# 2_MCU.net
KiCad netlist of a schematic drawn in Altium Designer
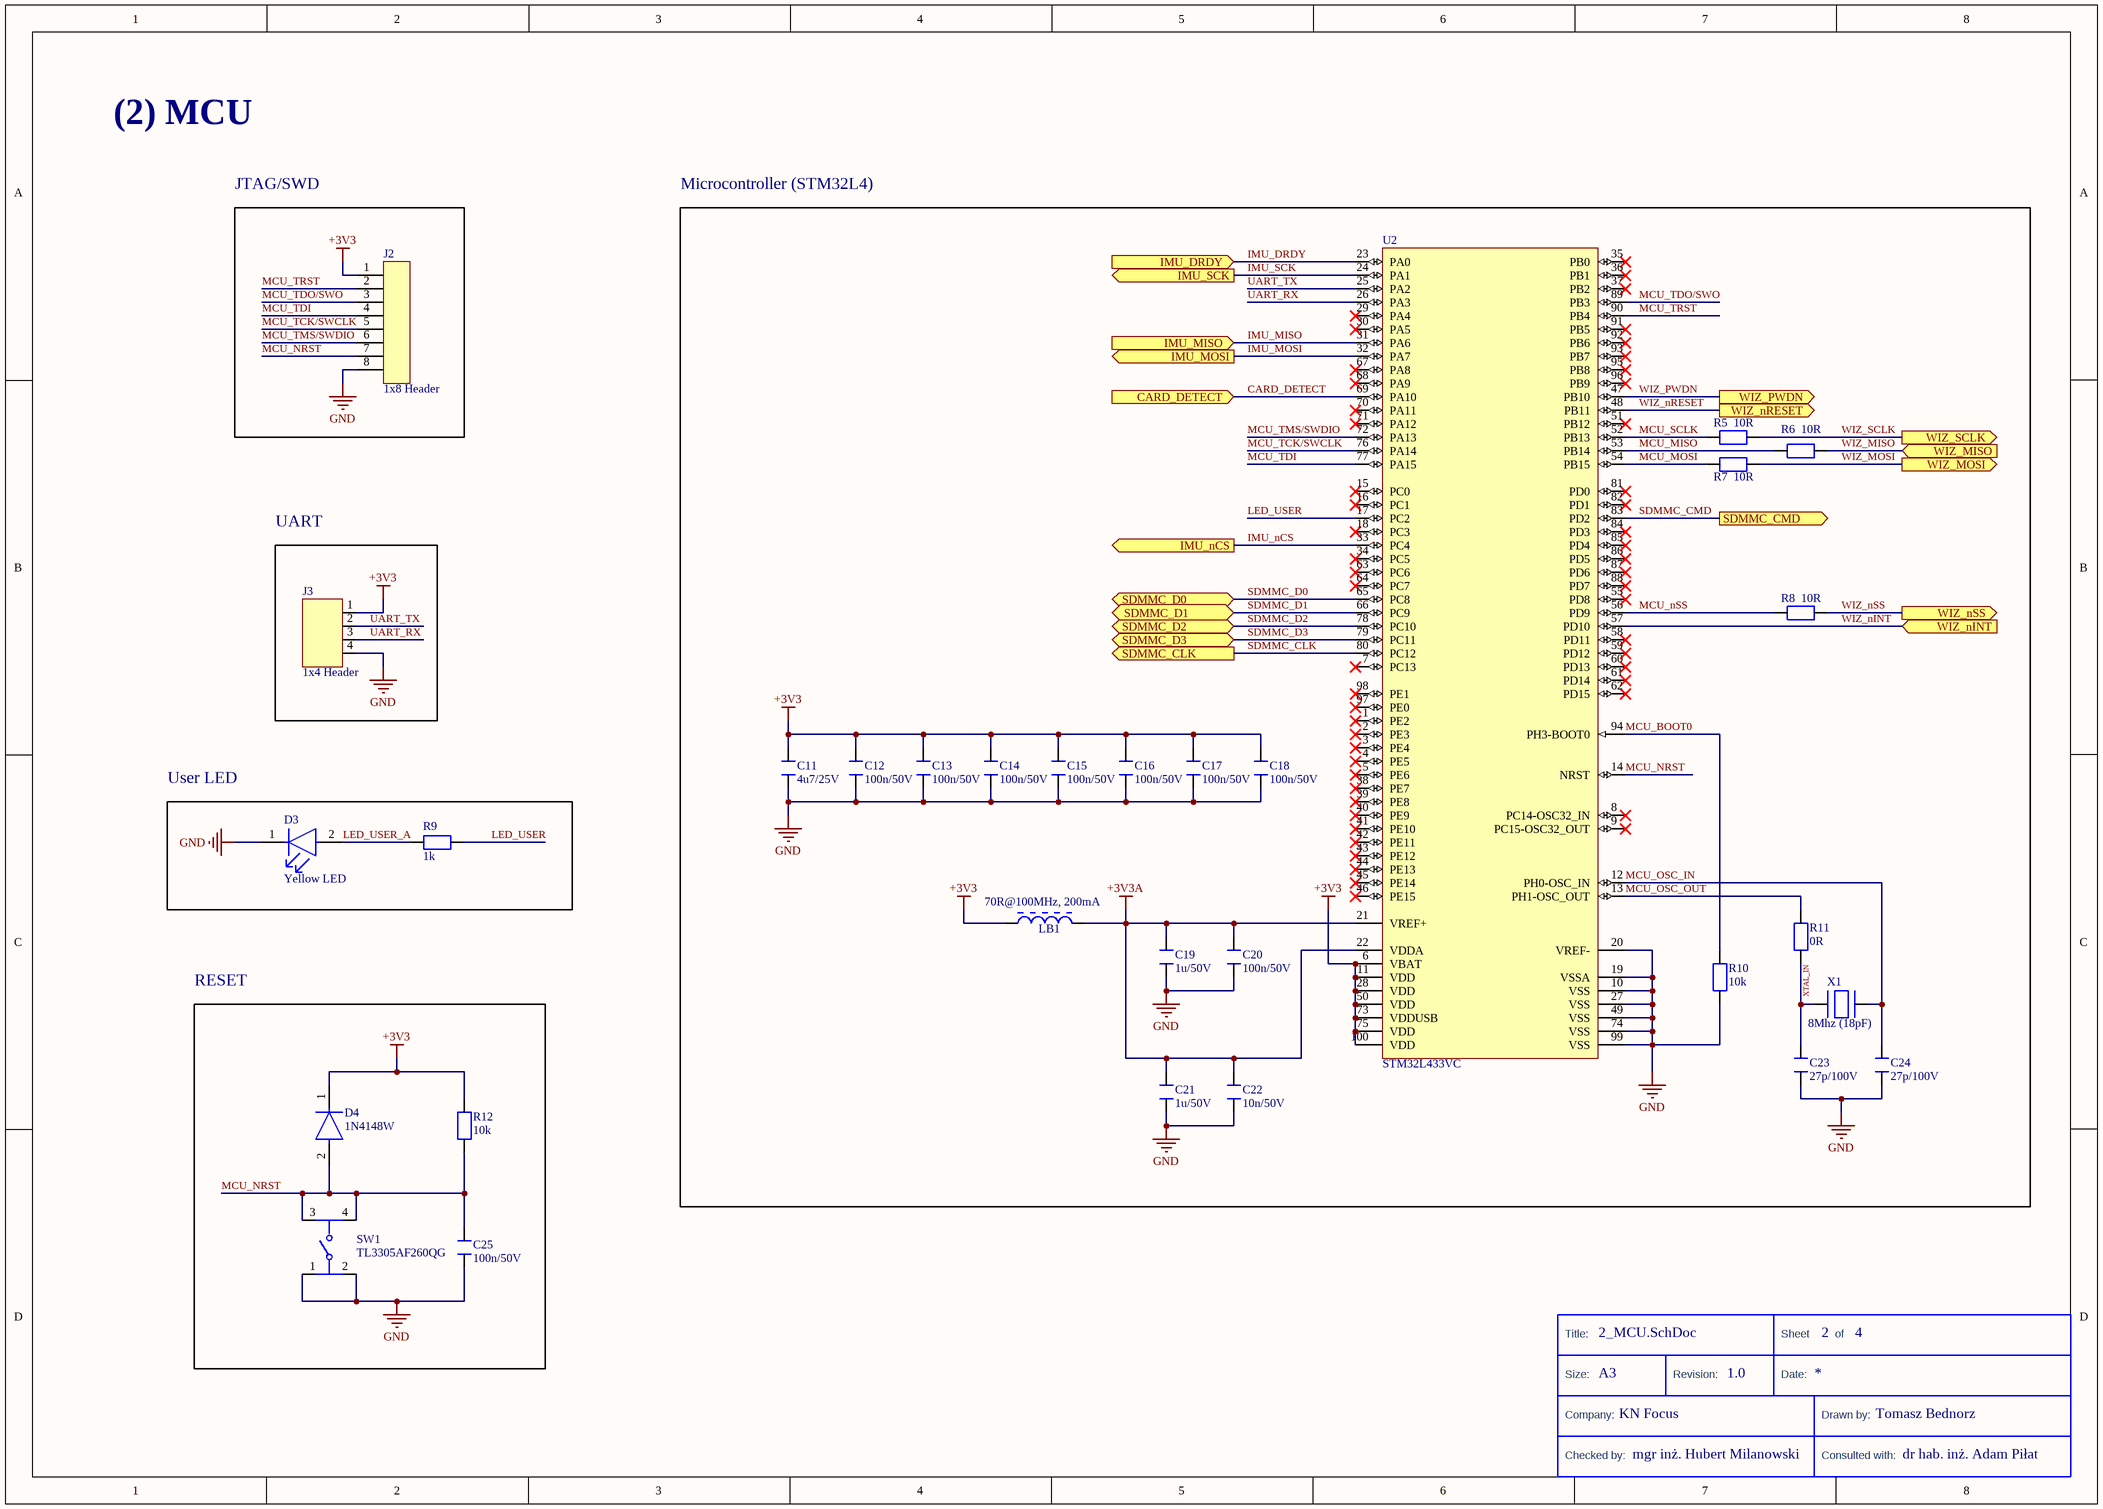
[diagram p0: 2_MCU.SchDoc]

(export (version "E")
  (design (tool "Eeschema 10.0.6"))
  (components
    (comp (ref "C11")
      (value "4u7/25V")
      (footprint "CAP_1206")
      (description "Generic 1206/3216 capacitor")
      (libsource (lib "SymbolLib") (part "CAP_1206"))
    )
    (comp (ref "C12")
      (value "100n/50V")
      (footprint "CAP_1206")
      (description "Generic 1206/3216 capacitor")
      (libsource (lib "SymbolLib") (part "CAP_1206"))
    )
    (comp (ref "C13")
      (value "100n/50V")
      (footprint "CAP_1206")
      (description "Generic 1206/3216 capacitor")
      (libsource (lib "SymbolLib") (part "CAP_1206"))
    )
    (comp (ref "C14")
      (value "100n/50V")
      (footprint "CAP_1206")
      (description "Generic 1206/3216 capacitor")
      (libsource (lib "SymbolLib") (part "CAP_1206"))
    )
    (comp (ref "C15")
      (value "100n/50V")
      (footprint "CAP_1206")
      (description "Generic 1206/3216 capacitor")
      (libsource (lib "SymbolLib") (part "CAP_1206"))
    )
    (comp (ref "C16")
      (value "100n/50V")
      (footprint "CAP_1206")
      (description "Generic 1206/3216 capacitor")
      (libsource (lib "SymbolLib") (part "CAP_1206"))
    )
    (comp (ref "C17")
      (value "100n/50V")
      (footprint "CAP_1206")
      (description "Generic 1206/3216 capacitor")
      (libsource (lib "SymbolLib") (part "CAP_1206"))
    )
    (comp (ref "C18")
      (value "100n/50V")
      (footprint "CAP_1206")
      (description "Generic 1206/3216 capacitor")
      (libsource (lib "SymbolLib") (part "CAP_1206"))
    )
    (comp (ref "C19")
      (value "1u/50V")
      (footprint "CAP_1206")
      (description "Generic 1206/3216 capacitor")
      (libsource (lib "SymbolLib") (part "CAP_1206"))
    )
    (comp (ref "C20")
      (value "100n/50V")
      (footprint "CAP_1206")
      (description "Generic 1206/3216 capacitor")
      (libsource (lib "SymbolLib") (part "CAP_1206"))
    )
    (comp (ref "C21")
      (value "1u/50V")
      (footprint "CAP_1206")
      (description "Generic 1206/3216 capacitor")
      (libsource (lib "SymbolLib") (part "CAP_1206"))
    )
    (comp (ref "C22")
      (value "10n/50V")
      (footprint "CAP_1206")
      (description "Generic 1206/3216 capacitor")
      (libsource (lib "SymbolLib") (part "CAP_1206"))
    )
    (comp (ref "C23")
      (value "27p/100V")
      (footprint "CAP_1206")
      (description "Generic 1206/3216 capacitor")
      (libsource (lib "SymbolLib") (part "CAP_1206"))
    )
    (comp (ref "C24")
      (value "27p/100V")
      (footprint "CAP_1206")
      (description "Generic 1206/3216 capacitor")
      (libsource (lib "SymbolLib") (part "CAP_1206"))
    )
    (comp (ref "C25")
      (value "100n/50V")
      (footprint "CAP_1206")
      (description "Generic 1206/3216 capacitor")
      (libsource (lib "SymbolLib") (part "CAP_1206"))
    )
    (comp (ref "D3")
      (value "Yellow LED")
      (footprint "FP-LTST-C150KSKT-MFG")
      (description "LED YELLOW CLEAR 1206 SMD")
      (libsource (lib "Altium Content Vault") (part "8706943c75ba83719d021d2fdc84c58"))
    )
    (comp (ref "D4")
      (value "1N4148W")
      (footprint "FP-SOD-123-IPC_A")
      (description "DIODE GEN PURP 100V 150MA SOD123")
      (libsource (lib "Altium Content Vault") (part "d7152d700b627762746794eb795d46e"))
    )
    (comp (ref "J2")
      (value "1x8 Header")
      (footprint "1x8 Header")
      (description "1x8 Header,Through Hole (Goldpin 2.54m)")
      (libsource (lib "SymbolLib") (part "1x8 Header"))
    )
    (comp (ref "J3")
      (value "1x4 Header")
      (footprint "1x4 Header (Goldpin 2.54mm)")
      (description "1x4 Header,Through Hole (Goldpin 2.54mm)")
      (libsource (lib "SymbolLib") (part "1x4 Header (Goldpin 2.54mm)"))
    )
    (comp (ref "LB1")
      (value "70R@100MHz, 200mA")
      (footprint "MURA-BLM31A_L")
      (description "Chip Bead, 100 MHz, 200 mA, -55 to 125 degC, 2-Pin SMD (1206), RoHS, Tape and Reel")
      (fields (field (name "MANUFACTURER") "Murata") (field (name "TOLERANCE") "25%"))
      (libsource (lib "Altium Content Vault") (part "IND-FB-2"))
    )
    (comp (ref "R5")
      (value "10R")
      (footprint "RES_1206")
      (description "Generic 1206/3216 resistor")
      (libsource (lib "SymbolLib") (part "RES_1206"))
    )
    (comp (ref "R6")
      (value "10R")
      (footprint "RES_1206")
      (description "Generic 1206/3216 resistor")
      (libsource (lib "SymbolLib") (part "RES_1206"))
    )
    (comp (ref "R7")
      (value "10R")
      (footprint "RES_1206")
      (description "Generic 1206/3216 resistor")
      (libsource (lib "SymbolLib") (part "RES_1206"))
    )
    (comp (ref "R8")
      (value "10R")
      (footprint "RES_1206")
      (description "Generic 1206/3216 resistor")
      (libsource (lib "SymbolLib") (part "RES_1206"))
    )
    (comp (ref "R9")
      (value "1k")
      (footprint "RES_1206")
      (description "Generic 1206/3216 resistor")
      (libsource (lib "SymbolLib") (part "RES_1206"))
    )
    (comp (ref "R10")
      (value "10k")
      (footprint "RES_1206")
      (description "Generic 1206/3216 resistor")
      (libsource (lib "SymbolLib") (part "RES_1206"))
    )
    (comp (ref "R11")
      (value "0R")
      (footprint "RES_1206")
      (description "Generic 1206/3216 resistor")
      (libsource (lib "SymbolLib") (part "RES_1206"))
    )
    (comp (ref "R12")
      (value "10k")
      (footprint "RES_1206")
      (description "Generic 1206/3216 resistor")
      (libsource (lib "SymbolLib") (part "RES_1206"))
    )
    (comp (ref "SW1")
      (value "TL3305AF260QG")
      (footprint "FP-TL3305AF260QG-MFG")
      (description "SWITCH TACTILE SPST-NO 50MA 12V")
      (libsource (lib "Altium Content Vault") (part "b8895f3f4cefb76e1819d2863dba89b"))
    )
    (comp (ref "U2")
      (value "STM32L433VC")
      (footprint "LQFP100")
      (description "STM32L433RC, 80MHz, Coretx-M4")
      (libsource (lib "SymbolLib") (part "STM32L433VC"))
    )
    (comp (ref "X1")
      (value "8Mhz (18pF)")
      (footprint "XTAL-12.5x4.8")
      (description "XTAL-8MHz")
      (libsource (lib "SymbolLib") (part "XTAL-8MHz"))
    )
  )
  (nets
    (net (code "1") (name "+3V3") (class "Default")
      (node (ref "C11") (pin "2") (pinfunction "2_2") (pintype "passive"))
      (node (ref "C12") (pin "2") (pinfunction "2_2") (pintype "passive"))
      (node (ref "C13") (pin "2") (pinfunction "2_2") (pintype "passive"))
      (node (ref "C14") (pin "2") (pinfunction "2_2") (pintype "passive"))
      (node (ref "C15") (pin "2") (pinfunction "2_2") (pintype "passive"))
      (node (ref "C16") (pin "2") (pinfunction "2_2") (pintype "passive"))
      (node (ref "C17") (pin "2") (pinfunction "2_2") (pintype "passive"))
      (node (ref "C18") (pin "2") (pinfunction "2_2") (pintype "passive"))
      (node (ref "D4") (pin "1") (pinfunction "C_1") (pintype "passive"))
      (node (ref "J2") (pin "1") (pintype "passive"))
      (node (ref "J3") (pin "1") (pinfunction "1_1") (pintype "passive"))
      (node (ref "LB1") (pin "1") (pinfunction "1_1") (pintype "passive"))
      (node (ref "R12") (pin "2") (pinfunction "2_2") (pintype "passive"))
      (node (ref "U2") (pin "100") (pinfunction "VDD_100") (pintype "power_in"))
      (node (ref "U2") (pin "11") (pinfunction "VDD_11") (pintype "power_in"))
      (node (ref "U2") (pin "28") (pinfunction "VDD_28") (pintype "power_in"))
      (node (ref "U2") (pin "50") (pinfunction "VDD_50") (pintype "power_in"))
      (node (ref "U2") (pin "6") (pinfunction "VBAT_6") (pintype "power_in"))
      (node (ref "U2") (pin "73") (pinfunction "VDDUSB_73") (pintype "power_in"))
      (node (ref "U2") (pin "75") (pinfunction "VDD_75") (pintype "power_in"))
    )
    (net (code "2") (name "+3V3A") (class "Default")
      (node (ref "C19") (pin "2") (pinfunction "2_2") (pintype "passive"))
      (node (ref "C20") (pin "2") (pinfunction "2_2") (pintype "passive"))
      (node (ref "C21") (pin "2") (pinfunction "2_2") (pintype "passive"))
      (node (ref "C22") (pin "2") (pinfunction "2_2") (pintype "passive"))
      (node (ref "LB1") (pin "2") (pinfunction "2_2") (pintype "passive"))
      (node (ref "U2") (pin "21") (pinfunction "VREF+_21") (pintype "power_in"))
      (node (ref "U2") (pin "22") (pinfunction "VDDA_22") (pintype "power_in"))
    )
    (net (code "3") (name "/CARD_DETECT") (class "Default")
      (node (ref "U2") (pin "69") (pinfunction "PA10_69") (pintype "bidirectional"))
    )
    (net (code "4") (name "/IMU_DRDY") (class "Default")
      (node (ref "U2") (pin "23") (pinfunction "PA0_23") (pintype "bidirectional"))
    )
    (net (code "5") (name "/IMU_MISO") (class "Default")
      (node (ref "U2") (pin "31") (pinfunction "PA6_31") (pintype "bidirectional"))
    )
    (net (code "6") (name "/IMU_MOSI") (class "Default")
      (node (ref "U2") (pin "32") (pinfunction "PA7_32") (pintype "bidirectional"))
    )
    (net (code "7") (name "/IMU_SCK") (class "Default")
      (node (ref "U2") (pin "24") (pinfunction "PA1_24") (pintype "bidirectional"))
    )
    (net (code "8") (name "/IMU_nCS") (class "Default")
      (node (ref "U2") (pin "33") (pinfunction "PC4_33") (pintype "bidirectional"))
    )
    (net (code "9") (name "/LED_USER") (class "Default")
      (node (ref "R9") (pin "1") (pinfunction "1_1") (pintype "passive"))
      (node (ref "U2") (pin "17") (pinfunction "PC2_17") (pintype "bidirectional"))
    )
    (net (code "10") (name "/LED_USER_A") (class "Default")
      (node (ref "D3") (pin "2") (pinfunction "A_2") (pintype "passive"))
      (node (ref "R9") (pin "2") (pinfunction "2_2") (pintype "passive"))
    )
    (net (code "11") (name "/MCU_BOOT0") (class "Default")
      (node (ref "R10") (pin "2") (pinfunction "2_2") (pintype "passive"))
      (node (ref "U2") (pin "94") (pinfunction "PH3-BOOT0_94") (pintype "input"))
    )
    (net (code "12") (name "/MCU_MISO") (class "Default")
      (node (ref "R6") (pin "2") (pinfunction "2_2") (pintype "passive"))
      (node (ref "U2") (pin "53") (pinfunction "PB14_53") (pintype "bidirectional"))
    )
    (net (code "13") (name "/MCU_MOSI") (class "Default")
      (node (ref "R7") (pin "2") (pinfunction "2_2") (pintype "passive"))
      (node (ref "U2") (pin "54") (pinfunction "PB15_54") (pintype "bidirectional"))
    )
    (net (code "14") (name "/MCU_NRST") (class "Default")
      (node (ref "C25") (pin "2") (pinfunction "2_2") (pintype "passive"))
      (node (ref "D4") (pin "2") (pinfunction "A_2") (pintype "passive"))
      (node (ref "J2") (pin "7") (pintype "passive"))
      (node (ref "R12") (pin "1") (pinfunction "1_1") (pintype "passive"))
      (node (ref "SW1") (pin "3") (pinfunction "3_3") (pintype "passive"))
      (node (ref "SW1") (pin "4") (pinfunction "4_4") (pintype "passive"))
      (node (ref "U2") (pin "14") (pinfunction "NRST_14") (pintype "bidirectional"))
    )
    (net (code "15") (name "/MCU_OSC_IN") (class "Default")
      (node (ref "C24") (pin "2") (pinfunction "2_2") (pintype "passive"))
      (node (ref "U2") (pin "12") (pinfunction "PH0-OSC_IN_12") (pintype "bidirectional"))
      (node (ref "X1") (pin "2") (pinfunction "2_2") (pintype "passive"))
    )
    (net (code "16") (name "/MCU_OSC_OUT") (class "Default")
      (node (ref "R11") (pin "1") (pinfunction "1_1") (pintype "passive"))
      (node (ref "U2") (pin "13") (pinfunction "PH1-OSC_OUT_13") (pintype "bidirectional"))
    )
    (net (code "17") (name "/MCU_SCLK") (class "Default")
      (node (ref "R5") (pin "2") (pinfunction "2_2") (pintype "passive"))
      (node (ref "U2") (pin "52") (pinfunction "PB13_52") (pintype "bidirectional"))
    )
    (net (code "18") (name "/MCU_TCK{slash}SWCLK") (class "Default")
      (node (ref "J2") (pin "5") (pintype "passive"))
      (node (ref "U2") (pin "76") (pinfunction "PA14_76") (pintype "bidirectional"))
    )
    (net (code "19") (name "/MCU_TDI") (class "Default")
      (node (ref "J2") (pin "4") (pintype "passive"))
      (node (ref "U2") (pin "77") (pinfunction "PA15_77") (pintype "bidirectional"))
    )
    (net (code "20") (name "/MCU_TDO{slash}SWO") (class "Default")
      (node (ref "J2") (pin "3") (pintype "passive"))
      (node (ref "U2") (pin "89") (pinfunction "PB3_89") (pintype "bidirectional"))
    )
    (net (code "21") (name "/MCU_TMS{slash}SWDIO") (class "Default")
      (node (ref "J2") (pin "6") (pintype "passive"))
      (node (ref "U2") (pin "72") (pinfunction "PA13_72") (pintype "bidirectional"))
    )
    (net (code "22") (name "/MCU_TRST") (class "Default")
      (node (ref "J2") (pin "2") (pintype "passive"))
      (node (ref "U2") (pin "90") (pinfunction "PB4_90") (pintype "bidirectional"))
    )
    (net (code "23") (name "/MCU_nSS") (class "Default")
      (node (ref "R8") (pin "2") (pinfunction "2_2") (pintype "passive"))
      (node (ref "U2") (pin "56") (pinfunction "PD9_56") (pintype "bidirectional"))
    )
    (net (code "24") (name "/SDMMC_CLK") (class "Default")
      (node (ref "U2") (pin "80") (pinfunction "PC12_80") (pintype "bidirectional"))
    )
    (net (code "25") (name "/SDMMC_CMD") (class "Default")
      (node (ref "U2") (pin "83") (pinfunction "PD2_83") (pintype "bidirectional"))
    )
    (net (code "26") (name "/SDMMC_D0") (class "Default")
      (node (ref "U2") (pin "65") (pinfunction "PC8_65") (pintype "bidirectional"))
    )
    (net (code "27") (name "/SDMMC_D1") (class "Default")
      (node (ref "U2") (pin "66") (pinfunction "PC9_66") (pintype "bidirectional"))
    )
    (net (code "28") (name "/SDMMC_D2") (class "Default")
      (node (ref "U2") (pin "78") (pinfunction "PC10_78") (pintype "bidirectional"))
    )
    (net (code "29") (name "/SDMMC_D3") (class "Default")
      (node (ref "U2") (pin "79") (pinfunction "PC11_79") (pintype "bidirectional"))
    )
    (net (code "30") (name "/UART_RX") (class "Default")
      (node (ref "J3") (pin "3") (pinfunction "3_3") (pintype "passive"))
      (node (ref "U2") (pin "26") (pinfunction "PA3_26") (pintype "bidirectional"))
    )
    (net (code "31") (name "/UART_TX") (class "Default")
      (node (ref "J3") (pin "2") (pinfunction "2_2") (pintype "passive"))
      (node (ref "U2") (pin "25") (pinfunction "PA2_25") (pintype "bidirectional"))
    )
    (net (code "32") (name "/WIZ_MISO") (class "Default")
      (node (ref "R6") (pin "1") (pinfunction "1_1") (pintype "passive"))
    )
    (net (code "33") (name "/WIZ_MOSI") (class "Default")
      (node (ref "R7") (pin "1") (pinfunction "1_1") (pintype "passive"))
    )
    (net (code "34") (name "/WIZ_PWDN") (class "Default")
      (node (ref "U2") (pin "47") (pinfunction "PB10_47") (pintype "bidirectional"))
    )
    (net (code "35") (name "/WIZ_SCLK") (class "Default")
      (node (ref "R5") (pin "1") (pinfunction "1_1") (pintype "passive"))
    )
    (net (code "36") (name "/WIZ_nINT") (class "Default")
      (node (ref "U2") (pin "57") (pinfunction "PD10_57") (pintype "bidirectional"))
    )
    (net (code "37") (name "/WIZ_nRESET") (class "Default")
      (node (ref "U2") (pin "48") (pinfunction "PB11_48") (pintype "bidirectional"))
    )
    (net (code "38") (name "/WIZ_nSS") (class "Default")
      (node (ref "R8") (pin "1") (pinfunction "1_1") (pintype "passive"))
    )
    (net (code "39") (name "/XTAL_IN") (class "Default")
      (node (ref "C23") (pin "2") (pinfunction "2_2") (pintype "passive"))
      (node (ref "R11") (pin "2") (pinfunction "2_2") (pintype "passive"))
      (node (ref "X1") (pin "1") (pinfunction "1_1") (pintype "passive"))
    )
    (net (code "40") (name "GND") (class "Default")
      (node (ref "C11") (pin "1") (pinfunction "1_1") (pintype "passive"))
      (node (ref "C12") (pin "1") (pinfunction "1_1") (pintype "passive"))
      (node (ref "C13") (pin "1") (pinfunction "1_1") (pintype "passive"))
      (node (ref "C14") (pin "1") (pinfunction "1_1") (pintype "passive"))
      (node (ref "C15") (pin "1") (pinfunction "1_1") (pintype "passive"))
      (node (ref "C16") (pin "1") (pinfunction "1_1") (pintype "passive"))
      (node (ref "C17") (pin "1") (pinfunction "1_1") (pintype "passive"))
      (node (ref "C18") (pin "1") (pinfunction "1_1") (pintype "passive"))
      (node (ref "C19") (pin "1") (pinfunction "1_1") (pintype "passive"))
      (node (ref "C20") (pin "1") (pinfunction "1_1") (pintype "passive"))
      (node (ref "C21") (pin "1") (pinfunction "1_1") (pintype "passive"))
      (node (ref "C22") (pin "1") (pinfunction "1_1") (pintype "passive"))
      (node (ref "C23") (pin "1") (pinfunction "1_1") (pintype "passive"))
      (node (ref "C24") (pin "1") (pinfunction "1_1") (pintype "passive"))
      (node (ref "C25") (pin "1") (pinfunction "1_1") (pintype "passive"))
      (node (ref "D3") (pin "1") (pinfunction "C_1") (pintype "passive"))
      (node (ref "J2") (pin "8") (pintype "passive"))
      (node (ref "J3") (pin "4") (pinfunction "4_4") (pintype "passive"))
      (node (ref "R10") (pin "1") (pinfunction "1_1") (pintype "passive"))
      (node (ref "SW1") (pin "1") (pinfunction "1_1") (pintype "passive"))
      (node (ref "SW1") (pin "2") (pinfunction "2_2") (pintype "passive"))
      (node (ref "U2") (pin "10") (pinfunction "VSS_10") (pintype "power_in"))
      (node (ref "U2") (pin "19") (pinfunction "VSSA_19") (pintype "power_in"))
      (node (ref "U2") (pin "20") (pinfunction "VREF-_20") (pintype "power_in"))
      (node (ref "U2") (pin "27") (pinfunction "VSS_27") (pintype "power_in"))
      (node (ref "U2") (pin "49") (pinfunction "VSS_49") (pintype "power_in"))
      (node (ref "U2") (pin "74") (pinfunction "VSS_74") (pintype "power_in"))
      (node (ref "U2") (pin "99") (pinfunction "VSS_99") (pintype "power_in"))
    )
    (net (code "41") (name "unconnected-(U2-PA4-Pad29)") (class "Default")
      (node (ref "U2") (pin "29") (pinfunction "PA4_29") (pintype "bidirectional+no_connect"))
    )
    (net (code "42") (name "unconnected-(U2-PA5-Pad30)") (class "Default")
      (node (ref "U2") (pin "30") (pinfunction "PA5_30") (pintype "bidirectional+no_connect"))
    )
    (net (code "43") (name "unconnected-(U2-PA8-Pad67)") (class "Default")
      (node (ref "U2") (pin "67") (pinfunction "PA8_67") (pintype "bidirectional+no_connect"))
    )
    (net (code "44") (name "unconnected-(U2-PA9-Pad68)") (class "Default")
      (node (ref "U2") (pin "68") (pinfunction "PA9_68") (pintype "bidirectional+no_connect"))
    )
    (net (code "45") (name "unconnected-(U2-PA11-Pad70)") (class "Default")
      (node (ref "U2") (pin "70") (pinfunction "PA11_70") (pintype "bidirectional+no_connect"))
    )
    (net (code "46") (name "unconnected-(U2-PA12-Pad71)") (class "Default")
      (node (ref "U2") (pin "71") (pinfunction "PA12_71") (pintype "bidirectional+no_connect"))
    )
    (net (code "47") (name "unconnected-(U2-PB0-Pad35)") (class "Default")
      (node (ref "U2") (pin "35") (pinfunction "PB0_35") (pintype "bidirectional+no_connect"))
    )
    (net (code "48") (name "unconnected-(U2-PB1-Pad36)") (class "Default")
      (node (ref "U2") (pin "36") (pinfunction "PB1_36") (pintype "bidirectional+no_connect"))
    )
    (net (code "49") (name "unconnected-(U2-PB2-Pad37)") (class "Default")
      (node (ref "U2") (pin "37") (pinfunction "PB2_37") (pintype "bidirectional+no_connect"))
    )
    (net (code "50") (name "unconnected-(U2-PB5-Pad91)") (class "Default")
      (node (ref "U2") (pin "91") (pinfunction "PB5_91") (pintype "bidirectional+no_connect"))
    )
    (net (code "51") (name "unconnected-(U2-PB6-Pad92)") (class "Default")
      (node (ref "U2") (pin "92") (pinfunction "PB6_92") (pintype "bidirectional+no_connect"))
    )
    (net (code "52") (name "unconnected-(U2-PB7-Pad93)") (class "Default")
      (node (ref "U2") (pin "93") (pinfunction "PB7_93") (pintype "bidirectional+no_connect"))
    )
    (net (code "53") (name "unconnected-(U2-PB8-Pad95)") (class "Default")
      (node (ref "U2") (pin "95") (pinfunction "PB8_95") (pintype "bidirectional+no_connect"))
    )
    (net (code "54") (name "unconnected-(U2-PB9-Pad96)") (class "Default")
      (node (ref "U2") (pin "96") (pinfunction "PB9_96") (pintype "bidirectional+no_connect"))
    )
    (net (code "55") (name "unconnected-(U2-PB12-Pad51)") (class "Default")
      (node (ref "U2") (pin "51") (pinfunction "PB12_51") (pintype "bidirectional+no_connect"))
    )
    (net (code "56") (name "unconnected-(U2-PC0-Pad15)") (class "Default")
      (node (ref "U2") (pin "15") (pinfunction "PC0_15") (pintype "bidirectional+no_connect"))
    )
    (net (code "57") (name "unconnected-(U2-PC1-Pad16)") (class "Default")
      (node (ref "U2") (pin "16") (pinfunction "PC1_16") (pintype "bidirectional+no_connect"))
    )
    (net (code "58") (name "unconnected-(U2-PC3-Pad18)") (class "Default")
      (node (ref "U2") (pin "18") (pinfunction "PC3_18") (pintype "bidirectional+no_connect"))
    )
    (net (code "59") (name "unconnected-(U2-PC5-Pad34)") (class "Default")
      (node (ref "U2") (pin "34") (pinfunction "PC5_34") (pintype "bidirectional+no_connect"))
    )
    (net (code "60") (name "unconnected-(U2-PC6-Pad63)") (class "Default")
      (node (ref "U2") (pin "63") (pinfunction "PC6_63") (pintype "bidirectional+no_connect"))
    )
    (net (code "61") (name "unconnected-(U2-PC7-Pad64)") (class "Default")
      (node (ref "U2") (pin "64") (pinfunction "PC7_64") (pintype "bidirectional+no_connect"))
    )
    (net (code "62") (name "unconnected-(U2-PC13-Pad7)") (class "Default")
      (node (ref "U2") (pin "7") (pinfunction "PC13_7") (pintype "bidirectional+no_connect"))
    )
    (net (code "63") (name "unconnected-(U2-PC14-OSC32_IN-Pad8)") (class "Default")
      (node (ref "U2") (pin "8") (pinfunction "PC14-OSC32_IN_8") (pintype "bidirectional+no_connect"))
    )
    (net (code "64") (name "unconnected-(U2-PC15-OSC32_OUT-Pad9)") (class "Default")
      (node (ref "U2") (pin "9") (pinfunction "PC15-OSC32_OUT_9") (pintype "bidirectional+no_connect"))
    )
    (net (code "65") (name "unconnected-(U2-PD0-Pad81)") (class "Default")
      (node (ref "U2") (pin "81") (pinfunction "PD0_81") (pintype "bidirectional+no_connect"))
    )
    (net (code "66") (name "unconnected-(U2-PD1-Pad82)") (class "Default")
      (node (ref "U2") (pin "82") (pinfunction "PD1_82") (pintype "bidirectional+no_connect"))
    )
    (net (code "67") (name "unconnected-(U2-PD3-Pad84)") (class "Default")
      (node (ref "U2") (pin "84") (pinfunction "PD3_84") (pintype "bidirectional+no_connect"))
    )
    (net (code "68") (name "unconnected-(U2-PD4-Pad85)") (class "Default")
      (node (ref "U2") (pin "85") (pinfunction "PD4_85") (pintype "bidirectional+no_connect"))
    )
    (net (code "69") (name "unconnected-(U2-PD5-Pad86)") (class "Default")
      (node (ref "U2") (pin "86") (pinfunction "PD5_86") (pintype "bidirectional+no_connect"))
    )
    (net (code "70") (name "unconnected-(U2-PD6-Pad87)") (class "Default")
      (node (ref "U2") (pin "87") (pinfunction "PD6_87") (pintype "bidirectional+no_connect"))
    )
    (net (code "71") (name "unconnected-(U2-PD7-Pad88)") (class "Default")
      (node (ref "U2") (pin "88") (pinfunction "PD7_88") (pintype "bidirectional+no_connect"))
    )
    (net (code "72") (name "unconnected-(U2-PD8-Pad55)") (class "Default")
      (node (ref "U2") (pin "55") (pinfunction "PD8_55") (pintype "bidirectional+no_connect"))
    )
    (net (code "73") (name "unconnected-(U2-PD11-Pad58)") (class "Default")
      (node (ref "U2") (pin "58") (pinfunction "PD11_58") (pintype "bidirectional+no_connect"))
    )
    (net (code "74") (name "unconnected-(U2-PD12-Pad59)") (class "Default")
      (node (ref "U2") (pin "59") (pinfunction "PD12_59") (pintype "bidirectional+no_connect"))
    )
    (net (code "75") (name "unconnected-(U2-PD13-Pad60)") (class "Default")
      (node (ref "U2") (pin "60") (pinfunction "PD13_60") (pintype "bidirectional+no_connect"))
    )
    (net (code "76") (name "unconnected-(U2-PD14-Pad61)") (class "Default")
      (node (ref "U2") (pin "61") (pinfunction "PD14_61") (pintype "bidirectional+no_connect"))
    )
    (net (code "77") (name "unconnected-(U2-PD15-Pad62)") (class "Default")
      (node (ref "U2") (pin "62") (pinfunction "PD15_62") (pintype "bidirectional+no_connect"))
    )
    (net (code "78") (name "unconnected-(U2-PE0-Pad97)") (class "Default")
      (node (ref "U2") (pin "97") (pinfunction "PE0_97") (pintype "bidirectional+no_connect"))
    )
    (net (code "79") (name "unconnected-(U2-PE1-Pad98)") (class "Default")
      (node (ref "U2") (pin "98") (pinfunction "PE1_98") (pintype "bidirectional+no_connect"))
    )
    (net (code "80") (name "unconnected-(U2-PE2-Pad1)") (class "Default")
      (node (ref "U2") (pin "1") (pinfunction "PE2_1") (pintype "bidirectional+no_connect"))
    )
    (net (code "81") (name "unconnected-(U2-PE3-Pad2)") (class "Default")
      (node (ref "U2") (pin "2") (pinfunction "PE3_2") (pintype "bidirectional+no_connect"))
    )
    (net (code "82") (name "unconnected-(U2-PE4-Pad3)") (class "Default")
      (node (ref "U2") (pin "3") (pinfunction "PE4_3") (pintype "bidirectional+no_connect"))
    )
    (net (code "83") (name "unconnected-(U2-PE5-Pad4)") (class "Default")
      (node (ref "U2") (pin "4") (pinfunction "PE5_4") (pintype "bidirectional+no_connect"))
    )
    (net (code "84") (name "unconnected-(U2-PE6-Pad5)") (class "Default")
      (node (ref "U2") (pin "5") (pinfunction "PE6_5") (pintype "bidirectional+no_connect"))
    )
    (net (code "85") (name "unconnected-(U2-PE7-Pad38)") (class "Default")
      (node (ref "U2") (pin "38") (pinfunction "PE7_38") (pintype "bidirectional+no_connect"))
    )
    (net (code "86") (name "unconnected-(U2-PE8-Pad39)") (class "Default")
      (node (ref "U2") (pin "39") (pinfunction "PE8_39") (pintype "bidirectional+no_connect"))
    )
    (net (code "87") (name "unconnected-(U2-PE9-Pad40)") (class "Default")
      (node (ref "U2") (pin "40") (pinfunction "PE9_40") (pintype "bidirectional+no_connect"))
    )
    (net (code "88") (name "unconnected-(U2-PE10-Pad41)") (class "Default")
      (node (ref "U2") (pin "41") (pinfunction "PE10_41") (pintype "bidirectional+no_connect"))
    )
    (net (code "89") (name "unconnected-(U2-PE11-Pad42)") (class "Default")
      (node (ref "U2") (pin "42") (pinfunction "PE11_42") (pintype "bidirectional+no_connect"))
    )
    (net (code "90") (name "unconnected-(U2-PE12-Pad43)") (class "Default")
      (node (ref "U2") (pin "43") (pinfunction "PE12_43") (pintype "bidirectional+no_connect"))
    )
    (net (code "91") (name "unconnected-(U2-PE13-Pad44)") (class "Default")
      (node (ref "U2") (pin "44") (pinfunction "PE13_44") (pintype "bidirectional+no_connect"))
    )
    (net (code "92") (name "unconnected-(U2-PE14-Pad45)") (class "Default")
      (node (ref "U2") (pin "45") (pinfunction "PE14_45") (pintype "bidirectional+no_connect"))
    )
    (net (code "93") (name "unconnected-(U2-PE15-Pad46)") (class "Default")
      (node (ref "U2") (pin "46") (pinfunction "PE15_46") (pintype "bidirectional+no_connect"))
    )
  )
)
